# Timer_PCB.net
KiCad netlist of a schematic drawn in EAGLE
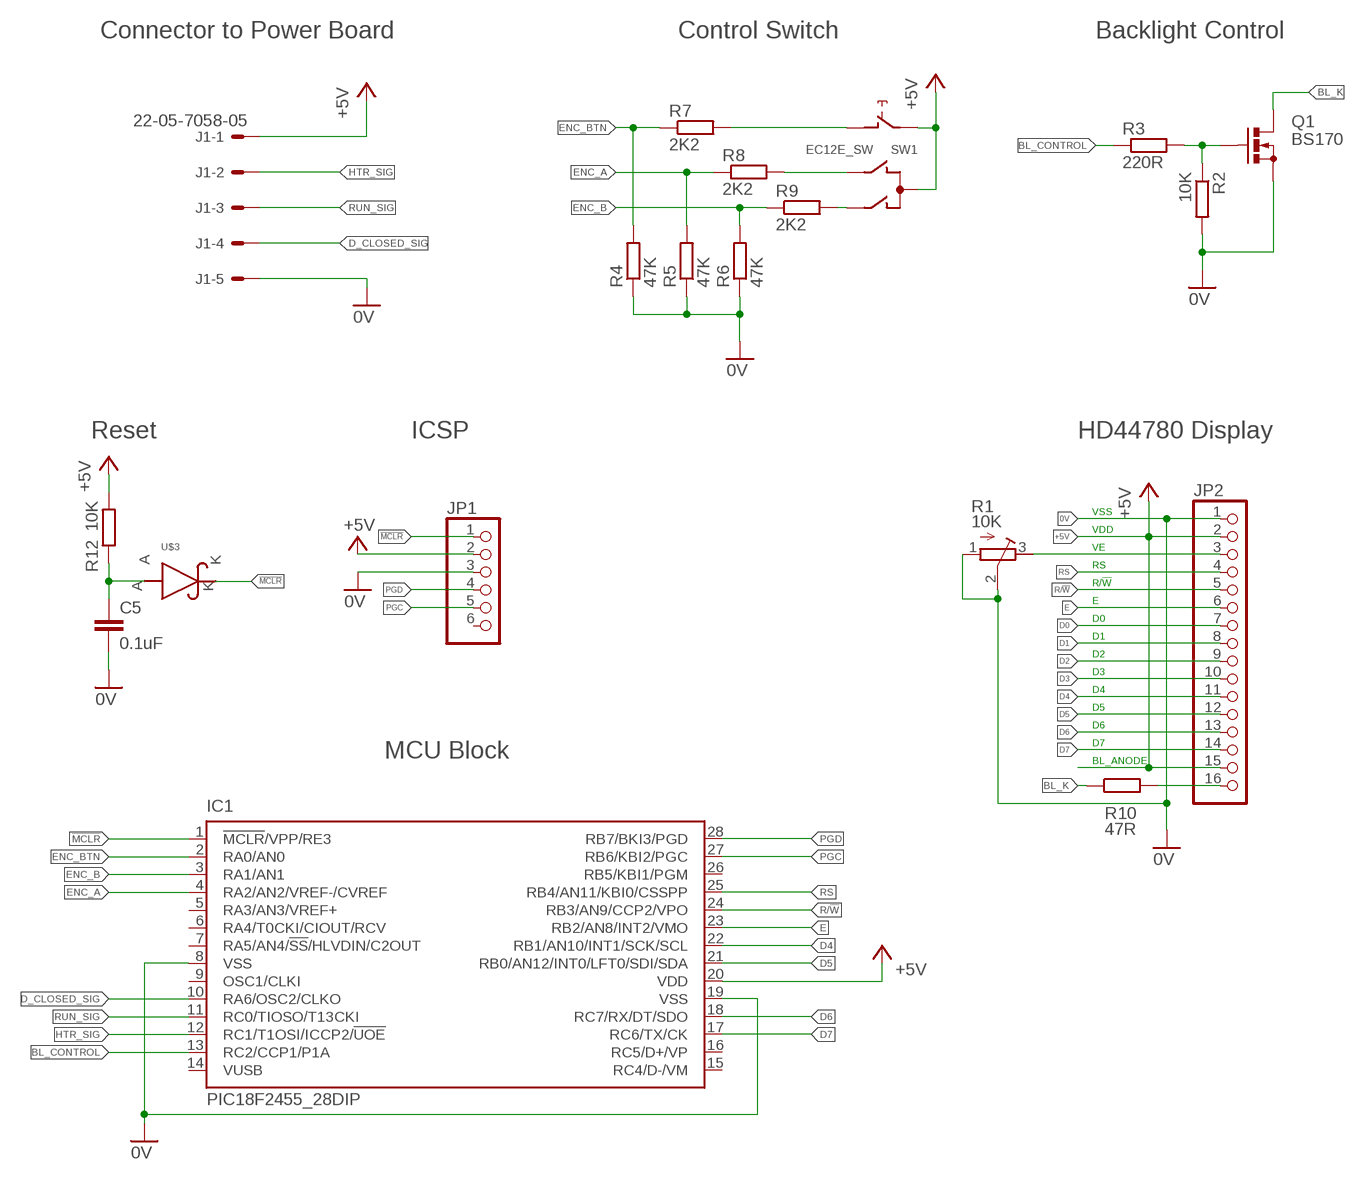
[diagram p0: schematic, sheet 1]

(export (version "E")
  (design (tool "Eeschema 10.0.6"))
  (components
    (comp (ref "C5")
      (value "0.1uF")
      (footprint "eagle-import:C0603")
      (libsource (lib "eagle-import") (part "C-EUC0603"))
    )
    (comp (ref "IC1")
      (value "PIC18F2455_28DIP")
      (footprint "eagle-import:DIL28-3")
      (fields (field (name "MF") "MICROCHIP") (field (name "MPN") "PIC18F2455-I/SP"))
      (libsource (lib "eagle-import") (part "PIC18F2_28DIP455"))
    )
    (comp (ref "J1")
      (value "22-05-7058-05")
      (footprint "eagle-import:7395-05")
      (libsource (lib "eagle-import") (part "22-?-0505-7058"))
    )
    (comp (ref "JP1")
      (value "PINHD-1X6/90")
      (footprint "eagle-import:1X06_90")
      (libsource (lib "eagle-import") (part "PINHD-1X6/90"))
    )
    (comp (ref "JP2")
      (value "PINHD-1X16")
      (footprint "eagle-import:1X16")
      (libsource (lib "eagle-import") (part "PINHD-1X16"))
    )
    (comp (ref "Q1")
      (value "BS170")
      (footprint "eagle-import:SOT54E")
      (libsource (lib "eagle-import") (part "BS170"))
    )
    (comp (ref "R1")
      (value "10K")
      (footprint "eagle-import:RTRIM64W")
      (libsource (lib "eagle-import") (part "R-TRIMM64W"))
    )
    (comp (ref "R2")
      (value "10K")
      (footprint "eagle-import:R0805")
      (libsource (lib "eagle-import") (part "R-EU_R0805"))
    )
    (comp (ref "R3")
      (value "220R")
      (footprint "eagle-import:R0805")
      (libsource (lib "eagle-import") (part "R-EU_R0805"))
    )
    (comp (ref "R4")
      (value "47K")
      (footprint "eagle-import:R0805")
      (libsource (lib "eagle-import") (part "R-EU_R0805"))
    )
    (comp (ref "R5")
      (value "47K")
      (footprint "eagle-import:R0805")
      (libsource (lib "eagle-import") (part "R-EU_R0805"))
    )
    (comp (ref "R6")
      (value "47K")
      (footprint "eagle-import:R0805")
      (libsource (lib "eagle-import") (part "R-EU_R0805"))
    )
    (comp (ref "R7")
      (value "2K2")
      (footprint "eagle-import:R0805")
      (libsource (lib "eagle-import") (part "R-EU_R0805"))
    )
    (comp (ref "R8")
      (value "2K2")
      (footprint "eagle-import:R0805")
      (libsource (lib "eagle-import") (part "R-EU_R0805"))
    )
    (comp (ref "R9")
      (value "2K2")
      (footprint "eagle-import:R0805")
      (libsource (lib "eagle-import") (part "R-EU_R0805"))
    )
    (comp (ref "R10")
      (value "47R")
      (footprint "eagle-import:0309_12")
      (libsource (lib "eagle-import") (part "R-EU_0309/12"))
    )
    (comp (ref "R12")
      (value "10K")
      (footprint "eagle-import:R0603")
      (libsource (lib "eagle-import") (part "R-EU_R0603"))
    )
    (comp (ref "SW1")
      (value "EC12E_SW")
      (footprint "eagle-import:ALPS_EC12E_SW")
      (fields (field (name "MPN") "EC12E2424407"))
      (libsource (lib "eagle-import") (part "EC12E_SW"))
    )
    (comp (ref "U$3")
      (value "ZHCS750")
      (footprint "eagle-import:SOT23")
      (libsource (lib "eagle-import") (part "ZHCS750"))
    )
  )
  (nets
    (net (code "1") (name "+5V") (class "Default")
      (node (ref "IC1") (pin "20") (pinfunction "VDD_20") (pintype "power_in"))
      (node (ref "J1") (pin "1") (pinfunction "S_1") (pintype "passive"))
      (node (ref "JP1") (pin "2") (pinfunction "2_2") (pintype "passive"))
      (node (ref "JP2") (pin "15") (pinfunction "15_15") (pintype "passive"))
      (node (ref "JP2") (pin "2") (pinfunction "2_2") (pintype "passive"))
      (node (ref "R12") (pin "2") (pinfunction "2_2") (pintype "passive"))
      (node (ref "SW1") (pin "C") (pinfunction "C_C") (pintype "passive"))
      (node (ref "SW1") (pin "E") (pinfunction "2_E") (pintype "passive"))
    )
    (net (code "2") (name "/R{slash}~{W}") (class "Default")
      (node (ref "IC1") (pin "24") (pinfunction "RB3/AN9/CCP2/VPO_24") (pintype "bidirectional"))
      (node (ref "JP2") (pin "5") (pinfunction "5_5") (pintype "passive"))
    )
    (net (code "3") (name "/~{MCLR}") (class "Default")
      (node (ref "IC1") (pin "1") (pinfunction "~{MCLR}/VPP/RE3_1") (pintype "input"))
      (node (ref "JP1") (pin "1") (pinfunction "1_1") (pintype "passive"))
      (node (ref "U$3") (pin "K") (pinfunction "K_K") (pintype "bidirectional"))
    )
    (net (code "4") (name "0V") (class "Default")
      (node (ref "C5") (pin "2") (pinfunction "2_2") (pintype "passive"))
      (node (ref "IC1") (pin "19") (pinfunction "VSS_19") (pintype "power_in"))
      (node (ref "IC1") (pin "8") (pinfunction "VSS_8") (pintype "power_in"))
      (node (ref "J1") (pin "5") (pinfunction "S_5") (pintype "passive"))
      (node (ref "JP1") (pin "3") (pinfunction "3_3") (pintype "passive"))
      (node (ref "JP2") (pin "1") (pinfunction "1_1") (pintype "passive"))
      (node (ref "Q1") (pin "S") (pinfunction "S_S") (pintype "passive"))
      (node (ref "R1") (pin "1") (pinfunction "E_1") (pintype "passive"))
      (node (ref "R1") (pin "2") (pinfunction "S_2") (pintype "passive"))
      (node (ref "R2") (pin "2") (pinfunction "2_2") (pintype "passive"))
      (node (ref "R4") (pin "1") (pinfunction "1_1") (pintype "passive"))
      (node (ref "R5") (pin "1") (pinfunction "1_1") (pintype "passive"))
      (node (ref "R6") (pin "1") (pinfunction "1_1") (pintype "passive"))
    )
    (net (code "5") (name "BL_CONTROL") (class "Default")
      (node (ref "IC1") (pin "13") (pinfunction "RC2/CCP1/P1A_13") (pintype "bidirectional"))
      (node (ref "R3") (pin "1") (pinfunction "1_1") (pintype "passive"))
    )
    (net (code "6") (name "BL_K") (class "Default")
      (node (ref "Q1") (pin "D") (pinfunction "D_D") (pintype "passive"))
      (node (ref "R10") (pin "1") (pinfunction "1_1") (pintype "passive"))
    )
    (net (code "7") (name "D0") (class "Default")
      (node (ref "JP2") (pin "7") (pinfunction "7_7") (pintype "passive"))
    )
    (net (code "8") (name "D1") (class "Default")
      (node (ref "JP2") (pin "8") (pinfunction "8_8") (pintype "passive"))
    )
    (net (code "9") (name "D2") (class "Default")
      (node (ref "JP2") (pin "9") (pinfunction "9_9") (pintype "passive"))
    )
    (net (code "10") (name "D3") (class "Default")
      (node (ref "JP2") (pin "10") (pinfunction "10_10") (pintype "passive"))
    )
    (net (code "11") (name "D4") (class "Default")
      (node (ref "IC1") (pin "22") (pinfunction "RB1/AN10/INT1/SCK/SCL_22") (pintype "bidirectional"))
      (node (ref "JP2") (pin "11") (pinfunction "11_11") (pintype "passive"))
    )
    (net (code "12") (name "D5") (class "Default")
      (node (ref "IC1") (pin "21") (pinfunction "RB0/AN12/INT0/LFT0/SDI/SDA_21") (pintype "bidirectional"))
      (node (ref "JP2") (pin "12") (pinfunction "12_12") (pintype "passive"))
    )
    (net (code "13") (name "D6") (class "Default")
      (node (ref "IC1") (pin "18") (pinfunction "RC7/RX/DT/SDO_18") (pintype "bidirectional"))
      (node (ref "JP2") (pin "13") (pinfunction "13_13") (pintype "passive"))
    )
    (net (code "14") (name "D7") (class "Default")
      (node (ref "IC1") (pin "17") (pinfunction "RC6/TX/CK_17") (pintype "bidirectional"))
      (node (ref "JP2") (pin "14") (pinfunction "14_14") (pintype "passive"))
    )
    (net (code "15") (name "D_CLOSED_SIG") (class "Default")
      (node (ref "IC1") (pin "10") (pinfunction "RA6/OSC2/CLKO_10") (pintype "output"))
      (node (ref "J1") (pin "4") (pinfunction "S_4") (pintype "passive"))
    )
    (net (code "16") (name "E") (class "Default")
      (node (ref "IC1") (pin "23") (pinfunction "RB2/AN8/INT2/VMO_23") (pintype "bidirectional"))
      (node (ref "JP2") (pin "6") (pinfunction "6_6") (pintype "passive"))
    )
    (net (code "17") (name "ENC_A") (class "Default")
      (node (ref "IC1") (pin "4") (pinfunction "RA2/AN2/VREF-/CVREF_4") (pintype "bidirectional"))
      (node (ref "R5") (pin "2") (pinfunction "2_2") (pintype "passive"))
      (node (ref "R8") (pin "1") (pinfunction "1_1") (pintype "passive"))
    )
    (net (code "18") (name "ENC_B") (class "Default")
      (node (ref "IC1") (pin "3") (pinfunction "RA1/AN1_3") (pintype "bidirectional"))
      (node (ref "R6") (pin "2") (pinfunction "2_2") (pintype "passive"))
      (node (ref "R9") (pin "1") (pinfunction "1_1") (pintype "passive"))
    )
    (net (code "19") (name "ENC_BTN") (class "Default")
      (node (ref "IC1") (pin "2") (pinfunction "RA0/AN0_2") (pintype "bidirectional"))
      (node (ref "R4") (pin "2") (pinfunction "2_2") (pintype "passive"))
      (node (ref "R7") (pin "1") (pinfunction "1_1") (pintype "passive"))
    )
    (net (code "20") (name "HTR_SIG") (class "Default")
      (node (ref "IC1") (pin "12") (pinfunction "RC1/T1OSI/ICCP2/~{UOE}_12") (pintype "bidirectional"))
      (node (ref "J1") (pin "2") (pinfunction "S_2") (pintype "passive"))
    )
    (net (code "21") (name "Net-(C5-Pad1)") (class "Default")
      (node (ref "C5") (pin "1") (pinfunction "1_1") (pintype "passive"))
      (node (ref "R12") (pin "1") (pinfunction "1_1") (pintype "passive"))
      (node (ref "U$3") (pin "A") (pinfunction "A_A") (pintype "bidirectional"))
    )
    (net (code "22") (name "Net-(JP2-Pad16)") (class "Default")
      (node (ref "JP2") (pin "16") (pinfunction "16_16") (pintype "passive"))
      (node (ref "R10") (pin "2") (pinfunction "2_2") (pintype "passive"))
    )
    (net (code "23") (name "Net-(Q1-PadG)") (class "Default")
      (node (ref "Q1") (pin "G") (pinfunction "G_G") (pintype "passive"))
      (node (ref "R2") (pin "1") (pinfunction "1_1") (pintype "passive"))
      (node (ref "R3") (pin "2") (pinfunction "2_2") (pintype "passive"))
    )
    (net (code "24") (name "Net-(R1-A)") (class "Default")
      (node (ref "JP2") (pin "3") (pinfunction "3_3") (pintype "passive"))
      (node (ref "R1") (pin "3") (pinfunction "A_3") (pintype "passive"))
    )
    (net (code "25") (name "Net-(R8-Pad2)") (class "Default")
      (node (ref "R8") (pin "2") (pinfunction "2_2") (pintype "passive"))
      (node (ref "SW1") (pin "B") (pinfunction "B_B") (pintype "passive"))
    )
    (net (code "26") (name "Net-(R9-Pad2)") (class "Default")
      (node (ref "R9") (pin "2") (pinfunction "2_2") (pintype "passive"))
      (node (ref "SW1") (pin "A") (pinfunction "A_A") (pintype "passive"))
    )
    (net (code "27") (name "Net-(SW1B-1)") (class "Default")
      (node (ref "R7") (pin "2") (pinfunction "2_2") (pintype "passive"))
      (node (ref "SW1") (pin "D") (pinfunction "1_D") (pintype "passive"))
    )
    (net (code "28") (name "PGC") (class "Default")
      (node (ref "IC1") (pin "27") (pinfunction "RB6/KBI2/PGC_27") (pintype "bidirectional"))
      (node (ref "JP1") (pin "5") (pinfunction "5_5") (pintype "passive"))
    )
    (net (code "29") (name "PGD") (class "Default")
      (node (ref "IC1") (pin "28") (pinfunction "RB7/BKI3/PGD_28") (pintype "bidirectional"))
      (node (ref "JP1") (pin "4") (pinfunction "4_4") (pintype "passive"))
    )
    (net (code "30") (name "RS") (class "Default")
      (node (ref "IC1") (pin "25") (pinfunction "RB4/AN11/KBI0/CSSPP_25") (pintype "bidirectional"))
      (node (ref "JP2") (pin "4") (pinfunction "4_4") (pintype "passive"))
    )
    (net (code "31") (name "RUN_SIG") (class "Default")
      (node (ref "IC1") (pin "11") (pinfunction "RC0/TIOSO/T13CKI_11") (pintype "bidirectional"))
      (node (ref "J1") (pin "3") (pinfunction "S_3") (pintype "passive"))
    )
    (net (code "32") (name "unconnected-(IC1-OSC1{slash}CLKI-Pad9)") (class "Default")
      (node (ref "IC1") (pin "9") (pinfunction "OSC1/CLKI_9") (pintype "input"))
    )
    (net (code "33") (name "unconnected-(IC1-RA3{slash}AN3{slash}VREF+-Pad5)") (class "Default")
      (node (ref "IC1") (pin "5") (pinfunction "RA3/AN3/VREF+_5") (pintype "bidirectional"))
    )
    (net (code "34") (name "unconnected-(IC1-RA4{slash}T0CKI{slash}CIOUT{slash}RCV-Pad6)") (class "Default")
      (node (ref "IC1") (pin "6") (pinfunction "RA4/T0CKI/CIOUT/RCV_6") (pintype "bidirectional"))
    )
    (net (code "35") (name "unconnected-(IC1-RA5{slash}AN4{slash}~{SS}{slash}HLVDIN{slash}C2OUT-Pad7)") (class "Default")
      (node (ref "IC1") (pin "7") (pinfunction "RA5/AN4/~{SS}/HLVDIN/C2OUT_7") (pintype "bidirectional"))
    )
    (net (code "36") (name "unconnected-(IC1-RB5{slash}KBI1{slash}PGM-Pad26)") (class "Default")
      (node (ref "IC1") (pin "26") (pinfunction "RB5/KBI1/PGM_26") (pintype "bidirectional"))
    )
    (net (code "37") (name "unconnected-(IC1-RC4{slash}D-{slash}VM-Pad15)") (class "Default")
      (node (ref "IC1") (pin "15") (pinfunction "RC4/D-/VM_15") (pintype "bidirectional"))
    )
    (net (code "38") (name "unconnected-(IC1-RC5{slash}D+{slash}VP-Pad16)") (class "Default")
      (node (ref "IC1") (pin "16") (pinfunction "RC5/D+/VP_16") (pintype "bidirectional"))
    )
    (net (code "39") (name "unconnected-(IC1-VUSB-Pad14)") (class "Default")
      (node (ref "IC1") (pin "14") (pinfunction "VUSB_14") (pintype "bidirectional"))
    )
    (net (code "40") (name "unconnected-(JP1-Pad6)") (class "Default")
      (node (ref "JP1") (pin "6") (pinfunction "6_6") (pintype "passive"))
    )
  )
)
